# ArduFrauenfelderCNC_1_0__ArduinoProMicro.net
KiCad netlist of a schematic drawn in EAGLE
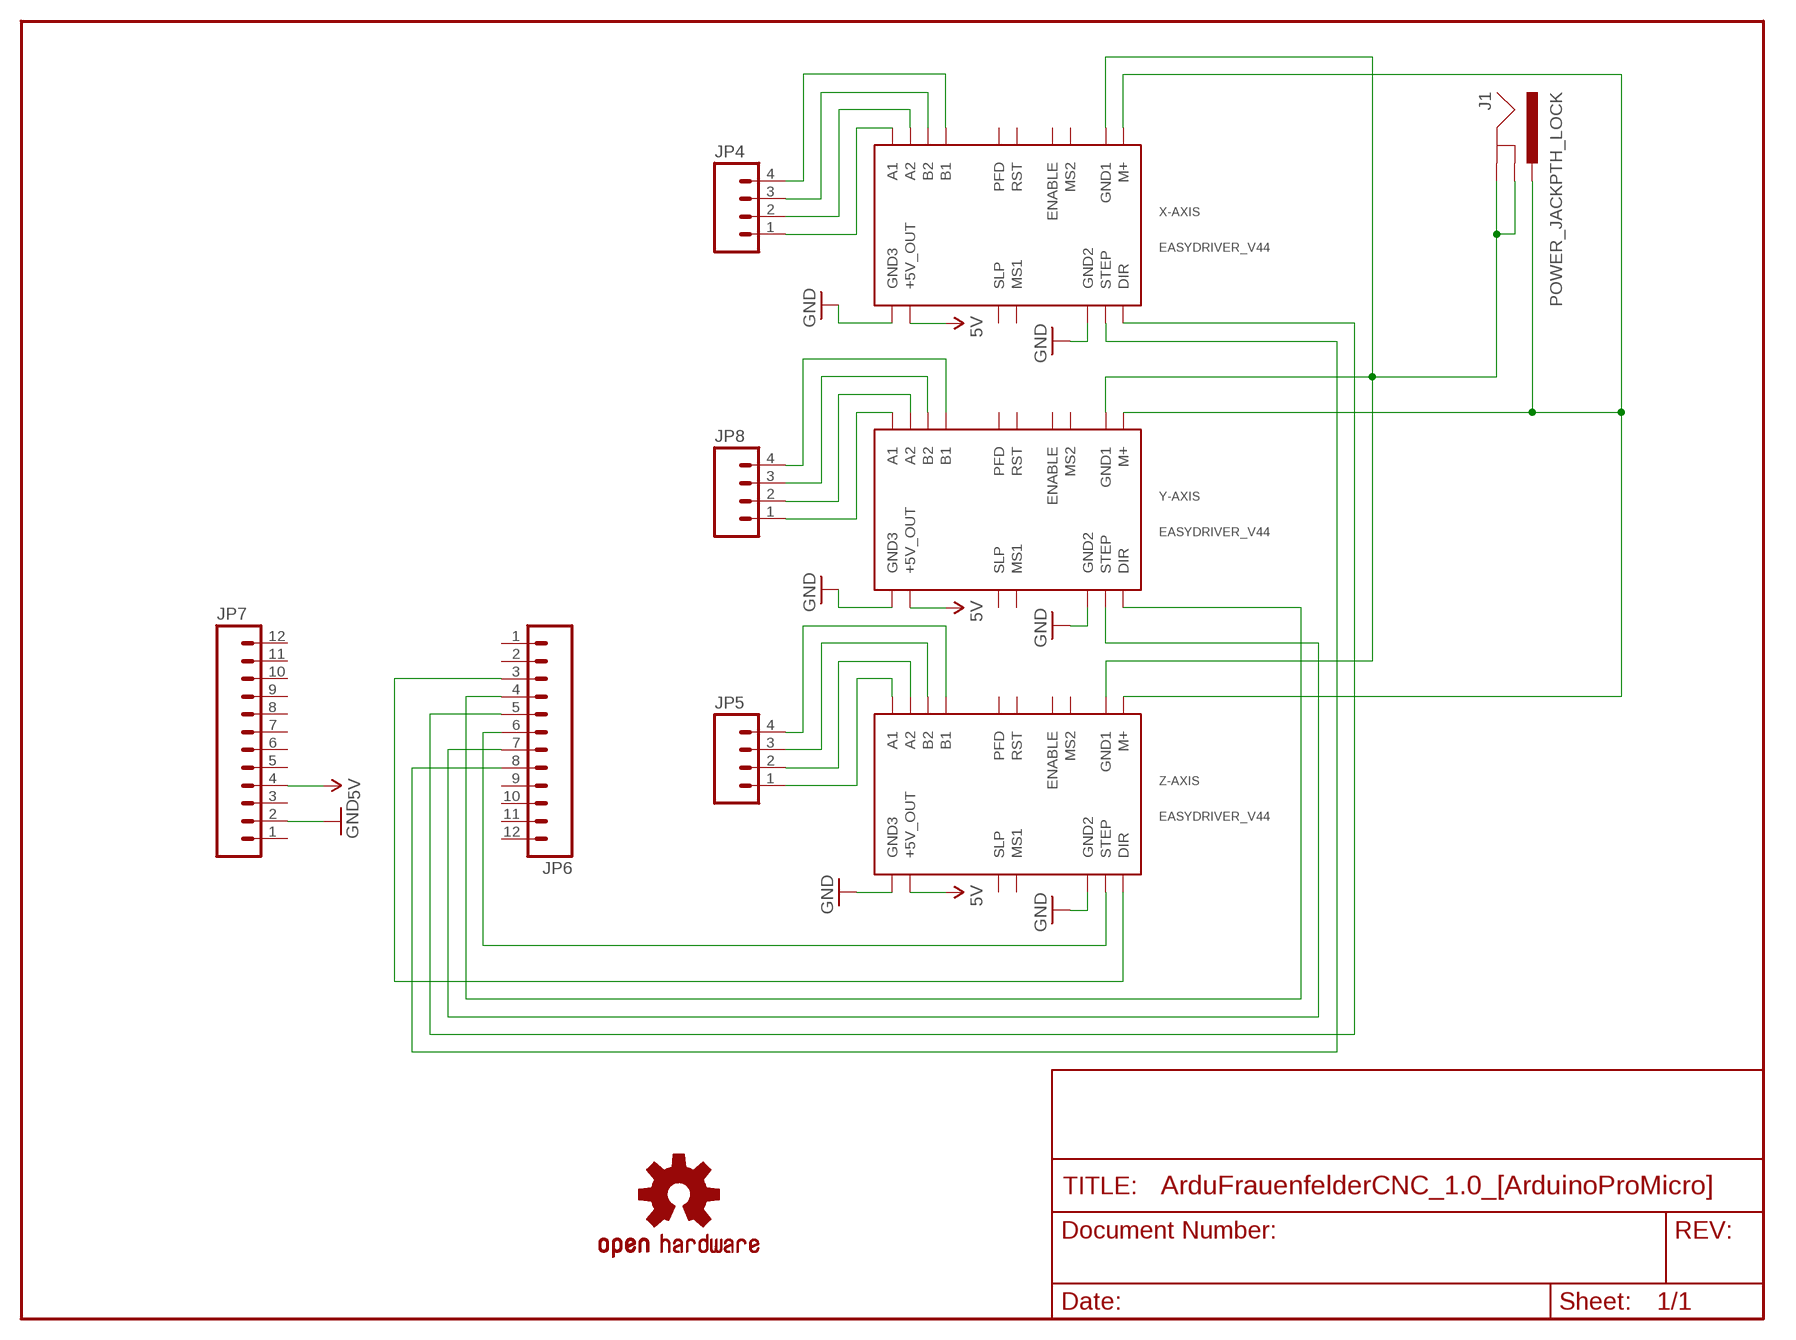
[diagram p0: schematic, sheet 1]

(export (version "E")
  (design (tool "Eeschema 10.0.6"))
  (components
    (comp (ref "J1")
      (value "POWER_JACKPTH_LOCK")
      (footprint "eagle-import:POWER_JACK_PTH_LOCK")
      (libsource (lib "eagle-import") (part "POWER_JACKPTH_LOCK"))
    )
    (comp (ref "JP4")
      (value "M04LOCK_LONGPADS")
      (footprint "eagle-import:1X04_LOCK_LONGPADS")
      (libsource (lib "eagle-import") (part "M04LOCK_LONGPADS"))
    )
    (comp (ref "JP5")
      (value "M04LOCK_LONGPADS")
      (footprint "eagle-import:1X04_LOCK_LONGPADS")
      (libsource (lib "eagle-import") (part "M04LOCK_LONGPADS"))
    )
    (comp (ref "JP6")
      (value "M12PTH")
      (footprint "eagle-import:1X12")
      (libsource (lib "eagle-import") (part "M12PTH"))
    )
    (comp (ref "JP7")
      (value "M12PTH")
      (footprint "eagle-import:1X12")
      (libsource (lib "eagle-import") (part "M12PTH"))
    )
    (comp (ref "JP8")
      (value "M04LOCK_LONGPADS")
      (footprint "eagle-import:1X04_LOCK_LONGPADS")
      (libsource (lib "eagle-import") (part "M04LOCK_LONGPADS"))
    )
    (comp (ref "U$2")
      (value "OSHW-LOGOM")
      (footprint "eagle-import:OSHW-LOGO-M")
      (libsource (lib "eagle-import") (part "OSHW-LOGOM"))
    )
    (comp (ref "X-AXIS")
      (value "EASYDRIVER_V44")
      (footprint "eagle-import:EASYDRIVER_V44")
      (libsource (lib "eagle-import") (part "EASYDRIVER_V44"))
    )
    (comp (ref "Y-AXIS")
      (value "EASYDRIVER_V44")
      (footprint "eagle-import:EASYDRIVER_V44")
      (libsource (lib "eagle-import") (part "EASYDRIVER_V44"))
    )
    (comp (ref "Z-AXIS")
      (value "EASYDRIVER_V44")
      (footprint "eagle-import:EASYDRIVER_V44")
      (libsource (lib "eagle-import") (part "EASYDRIVER_V44"))
    )
  )
  (nets
    (net (code "1") (name "5V") (class "Default")
      (node (ref "JP7") (pin "4") (pinfunction "4_4") (pintype "passive"))
      (node (ref "X-AXIS") (pin "P$11") (pinfunction "+5V_OUT_P$11") (pintype "bidirectional"))
      (node (ref "Y-AXIS") (pin "P$11") (pinfunction "+5V_OUT_P$11") (pintype "bidirectional"))
      (node (ref "Z-AXIS") (pin "P$11") (pinfunction "+5V_OUT_P$11") (pintype "bidirectional"))
    )
    (net (code "2") (name "GND") (class "Default")
      (node (ref "JP7") (pin "2") (pinfunction "2_2") (pintype "passive"))
      (node (ref "X-AXIS") (pin "GND2") (pinfunction "GND2_GND2") (pintype "bidirectional"))
      (node (ref "X-AXIS") (pin "GND3") (pinfunction "GND3_GND3") (pintype "bidirectional"))
      (node (ref "Y-AXIS") (pin "GND2") (pinfunction "GND2_GND2") (pintype "bidirectional"))
      (node (ref "Y-AXIS") (pin "GND3") (pinfunction "GND3_GND3") (pintype "bidirectional"))
      (node (ref "Z-AXIS") (pin "GND2") (pinfunction "GND2_GND2") (pintype "bidirectional"))
      (node (ref "Z-AXIS") (pin "GND3") (pinfunction "GND3_GND3") (pintype "bidirectional"))
    )
    (net (code "3") (name "Net-(J1-PadGND)") (class "Default")
      (node (ref "J1") (pin "GND") (pinfunction "GND_GND") (pintype "bidirectional"))
      (node (ref "J1") (pin "GNDBREAK") (pinfunction "GNDBREAK_GNDBREAK") (pintype "bidirectional"))
      (node (ref "X-AXIS") (pin "GND1") (pinfunction "GND1_GND1") (pintype "bidirectional"))
      (node (ref "Y-AXIS") (pin "GND1") (pinfunction "GND1_GND1") (pintype "bidirectional"))
      (node (ref "Z-AXIS") (pin "GND1") (pinfunction "GND1_GND1") (pintype "bidirectional"))
    )
    (net (code "4") (name "Net-(J1-PadPWR)") (class "Default")
      (node (ref "J1") (pin "PWR") (pinfunction "PWR_PWR") (pintype "bidirectional"))
      (node (ref "X-AXIS") (pin "M+") (pinfunction "M+_M+") (pintype "bidirectional"))
      (node (ref "Y-AXIS") (pin "M+") (pinfunction "M+_M+") (pintype "bidirectional"))
      (node (ref "Z-AXIS") (pin "M+") (pinfunction "M+_M+") (pintype "bidirectional"))
    )
    (net (code "5") (name "Net-(JP4-Pad1)") (class "Default")
      (node (ref "JP4") (pin "1") (pinfunction "1_1") (pintype "passive"))
      (node (ref "X-AXIS") (pin "A1") (pinfunction "A1_A1") (pintype "bidirectional"))
    )
    (net (code "6") (name "Net-(JP4-Pad2)") (class "Default")
      (node (ref "JP4") (pin "2") (pinfunction "2_2") (pintype "passive"))
      (node (ref "X-AXIS") (pin "A2") (pinfunction "A2_A2") (pintype "bidirectional"))
    )
    (net (code "7") (name "Net-(JP4-Pad3)") (class "Default")
      (node (ref "JP4") (pin "3") (pinfunction "3_3") (pintype "passive"))
      (node (ref "X-AXIS") (pin "B2") (pinfunction "B2_B2") (pintype "bidirectional"))
    )
    (net (code "8") (name "Net-(JP4-Pad4)") (class "Default")
      (node (ref "JP4") (pin "4") (pinfunction "4_4") (pintype "passive"))
      (node (ref "X-AXIS") (pin "B1") (pinfunction "B1_B1") (pintype "bidirectional"))
    )
    (net (code "9") (name "Net-(JP5-Pad1)") (class "Default")
      (node (ref "JP5") (pin "1") (pinfunction "1_1") (pintype "passive"))
      (node (ref "Z-AXIS") (pin "A1") (pinfunction "A1_A1") (pintype "bidirectional"))
    )
    (net (code "10") (name "Net-(JP5-Pad2)") (class "Default")
      (node (ref "JP5") (pin "2") (pinfunction "2_2") (pintype "passive"))
      (node (ref "Z-AXIS") (pin "A2") (pinfunction "A2_A2") (pintype "bidirectional"))
    )
    (net (code "11") (name "Net-(JP5-Pad3)") (class "Default")
      (node (ref "JP5") (pin "3") (pinfunction "3_3") (pintype "passive"))
      (node (ref "Z-AXIS") (pin "B2") (pinfunction "B2_B2") (pintype "bidirectional"))
    )
    (net (code "12") (name "Net-(JP5-Pad4)") (class "Default")
      (node (ref "JP5") (pin "4") (pinfunction "4_4") (pintype "passive"))
      (node (ref "Z-AXIS") (pin "B1") (pinfunction "B1_B1") (pintype "bidirectional"))
    )
    (net (code "13") (name "Net-(JP6-Pad3)") (class "Default")
      (node (ref "JP6") (pin "3") (pinfunction "3_3") (pintype "passive"))
      (node (ref "Z-AXIS") (pin "DIR") (pinfunction "DIR_DIR") (pintype "bidirectional"))
    )
    (net (code "14") (name "Net-(JP6-Pad4)") (class "Default")
      (node (ref "JP6") (pin "4") (pinfunction "4_4") (pintype "passive"))
      (node (ref "Y-AXIS") (pin "DIR") (pinfunction "DIR_DIR") (pintype "bidirectional"))
    )
    (net (code "15") (name "Net-(JP6-Pad5)") (class "Default")
      (node (ref "JP6") (pin "5") (pinfunction "5_5") (pintype "passive"))
      (node (ref "X-AXIS") (pin "DIR") (pinfunction "DIR_DIR") (pintype "bidirectional"))
    )
    (net (code "16") (name "Net-(JP6-Pad6)") (class "Default")
      (node (ref "JP6") (pin "6") (pinfunction "6_6") (pintype "passive"))
      (node (ref "Z-AXIS") (pin "STEP") (pinfunction "STEP_STEP") (pintype "bidirectional"))
    )
    (net (code "17") (name "Net-(JP6-Pad7)") (class "Default")
      (node (ref "JP6") (pin "7") (pinfunction "7_7") (pintype "passive"))
      (node (ref "Y-AXIS") (pin "STEP") (pinfunction "STEP_STEP") (pintype "bidirectional"))
    )
    (net (code "18") (name "Net-(JP6-Pad8)") (class "Default")
      (node (ref "JP6") (pin "8") (pinfunction "8_8") (pintype "passive"))
      (node (ref "X-AXIS") (pin "STEP") (pinfunction "STEP_STEP") (pintype "bidirectional"))
    )
    (net (code "19") (name "Net-(JP8-Pad1)") (class "Default")
      (node (ref "JP8") (pin "1") (pinfunction "1_1") (pintype "passive"))
      (node (ref "Y-AXIS") (pin "A1") (pinfunction "A1_A1") (pintype "bidirectional"))
    )
    (net (code "20") (name "Net-(JP8-Pad2)") (class "Default")
      (node (ref "JP8") (pin "2") (pinfunction "2_2") (pintype "passive"))
      (node (ref "Y-AXIS") (pin "A2") (pinfunction "A2_A2") (pintype "bidirectional"))
    )
    (net (code "21") (name "Net-(JP8-Pad3)") (class "Default")
      (node (ref "JP8") (pin "3") (pinfunction "3_3") (pintype "passive"))
      (node (ref "Y-AXIS") (pin "B2") (pinfunction "B2_B2") (pintype "bidirectional"))
    )
    (net (code "22") (name "Net-(JP8-Pad4)") (class "Default")
      (node (ref "JP8") (pin "4") (pinfunction "4_4") (pintype "passive"))
      (node (ref "Y-AXIS") (pin "B1") (pinfunction "B1_B1") (pintype "bidirectional"))
    )
    (net (code "23") (name "unconnected-(JP6-Pad1)") (class "Default")
      (node (ref "JP6") (pin "1") (pinfunction "1_1") (pintype "passive"))
    )
    (net (code "24") (name "unconnected-(JP6-Pad2)") (class "Default")
      (node (ref "JP6") (pin "2") (pinfunction "2_2") (pintype "passive"))
    )
    (net (code "25") (name "unconnected-(JP6-Pad9)") (class "Default")
      (node (ref "JP6") (pin "9") (pinfunction "9_9") (pintype "passive"))
    )
    (net (code "26") (name "unconnected-(JP6-Pad10)") (class "Default")
      (node (ref "JP6") (pin "10") (pinfunction "10_10") (pintype "passive"))
    )
    (net (code "27") (name "unconnected-(JP6-Pad11)") (class "Default")
      (node (ref "JP6") (pin "11") (pinfunction "11_11") (pintype "passive"))
    )
    (net (code "28") (name "unconnected-(JP6-Pad12)") (class "Default")
      (node (ref "JP6") (pin "12") (pinfunction "12_12") (pintype "passive"))
    )
    (net (code "29") (name "unconnected-(JP7-Pad1)") (class "Default")
      (node (ref "JP7") (pin "1") (pinfunction "1_1") (pintype "passive"))
    )
    (net (code "30") (name "unconnected-(JP7-Pad3)") (class "Default")
      (node (ref "JP7") (pin "3") (pinfunction "3_3") (pintype "passive"))
    )
    (net (code "31") (name "unconnected-(JP7-Pad5)") (class "Default")
      (node (ref "JP7") (pin "5") (pinfunction "5_5") (pintype "passive"))
    )
    (net (code "32") (name "unconnected-(JP7-Pad6)") (class "Default")
      (node (ref "JP7") (pin "6") (pinfunction "6_6") (pintype "passive"))
    )
    (net (code "33") (name "unconnected-(JP7-Pad7)") (class "Default")
      (node (ref "JP7") (pin "7") (pinfunction "7_7") (pintype "passive"))
    )
    (net (code "34") (name "unconnected-(JP7-Pad8)") (class "Default")
      (node (ref "JP7") (pin "8") (pinfunction "8_8") (pintype "passive"))
    )
    (net (code "35") (name "unconnected-(JP7-Pad9)") (class "Default")
      (node (ref "JP7") (pin "9") (pinfunction "9_9") (pintype "passive"))
    )
    (net (code "36") (name "unconnected-(JP7-Pad10)") (class "Default")
      (node (ref "JP7") (pin "10") (pinfunction "10_10") (pintype "passive"))
    )
    (net (code "37") (name "unconnected-(JP7-Pad11)") (class "Default")
      (node (ref "JP7") (pin "11") (pinfunction "11_11") (pintype "passive"))
    )
    (net (code "38") (name "unconnected-(JP7-Pad12)") (class "Default")
      (node (ref "JP7") (pin "12") (pinfunction "12_12") (pintype "passive"))
    )
    (net (code "39") (name "unconnected-(X-AXIS-PadENABLE)") (class "Default")
      (node (ref "X-AXIS") (pin "ENABLE") (pinfunction "ENABLE_ENABLE") (pintype "bidirectional"))
    )
    (net (code "40") (name "unconnected-(X-AXIS-PadMS1)") (class "Default")
      (node (ref "X-AXIS") (pin "MS1") (pinfunction "MS1_MS1") (pintype "bidirectional"))
    )
    (net (code "41") (name "unconnected-(X-AXIS-PadMS2)") (class "Default")
      (node (ref "X-AXIS") (pin "MS2") (pinfunction "MS2_MS2") (pintype "bidirectional"))
    )
    (net (code "42") (name "unconnected-(X-AXIS-PadPFD)") (class "Default")
      (node (ref "X-AXIS") (pin "PFD") (pinfunction "PFD_PFD") (pintype "bidirectional"))
    )
    (net (code "43") (name "unconnected-(X-AXIS-PadRST)") (class "Default")
      (node (ref "X-AXIS") (pin "RST") (pinfunction "RST_RST") (pintype "bidirectional"))
    )
    (net (code "44") (name "unconnected-(X-AXIS-SLP-PadSLEEP)") (class "Default")
      (node (ref "X-AXIS") (pin "SLEEP") (pinfunction "SLP_SLEEP") (pintype "bidirectional"))
    )
    (net (code "45") (name "unconnected-(Y-AXIS-PadENABLE)") (class "Default")
      (node (ref "Y-AXIS") (pin "ENABLE") (pinfunction "ENABLE_ENABLE") (pintype "bidirectional"))
    )
    (net (code "46") (name "unconnected-(Y-AXIS-PadMS1)") (class "Default")
      (node (ref "Y-AXIS") (pin "MS1") (pinfunction "MS1_MS1") (pintype "bidirectional"))
    )
    (net (code "47") (name "unconnected-(Y-AXIS-PadMS2)") (class "Default")
      (node (ref "Y-AXIS") (pin "MS2") (pinfunction "MS2_MS2") (pintype "bidirectional"))
    )
    (net (code "48") (name "unconnected-(Y-AXIS-PadPFD)") (class "Default")
      (node (ref "Y-AXIS") (pin "PFD") (pinfunction "PFD_PFD") (pintype "bidirectional"))
    )
    (net (code "49") (name "unconnected-(Y-AXIS-PadRST)") (class "Default")
      (node (ref "Y-AXIS") (pin "RST") (pinfunction "RST_RST") (pintype "bidirectional"))
    )
    (net (code "50") (name "unconnected-(Y-AXIS-SLP-PadSLEEP)") (class "Default")
      (node (ref "Y-AXIS") (pin "SLEEP") (pinfunction "SLP_SLEEP") (pintype "bidirectional"))
    )
    (net (code "51") (name "unconnected-(Z-AXIS-PadENABLE)") (class "Default")
      (node (ref "Z-AXIS") (pin "ENABLE") (pinfunction "ENABLE_ENABLE") (pintype "bidirectional"))
    )
    (net (code "52") (name "unconnected-(Z-AXIS-PadMS1)") (class "Default")
      (node (ref "Z-AXIS") (pin "MS1") (pinfunction "MS1_MS1") (pintype "bidirectional"))
    )
    (net (code "53") (name "unconnected-(Z-AXIS-PadMS2)") (class "Default")
      (node (ref "Z-AXIS") (pin "MS2") (pinfunction "MS2_MS2") (pintype "bidirectional"))
    )
    (net (code "54") (name "unconnected-(Z-AXIS-PadPFD)") (class "Default")
      (node (ref "Z-AXIS") (pin "PFD") (pinfunction "PFD_PFD") (pintype "bidirectional"))
    )
    (net (code "55") (name "unconnected-(Z-AXIS-PadRST)") (class "Default")
      (node (ref "Z-AXIS") (pin "RST") (pinfunction "RST_RST") (pintype "bidirectional"))
    )
    (net (code "56") (name "unconnected-(Z-AXIS-SLP-PadSLEEP)") (class "Default")
      (node (ref "Z-AXIS") (pin "SLEEP") (pinfunction "SLP_SLEEP") (pintype "bidirectional"))
    )
  )
)
